# JEEP_Aux_Control_PCB.net
KiCad netlist of a schematic drawn in EAGLE
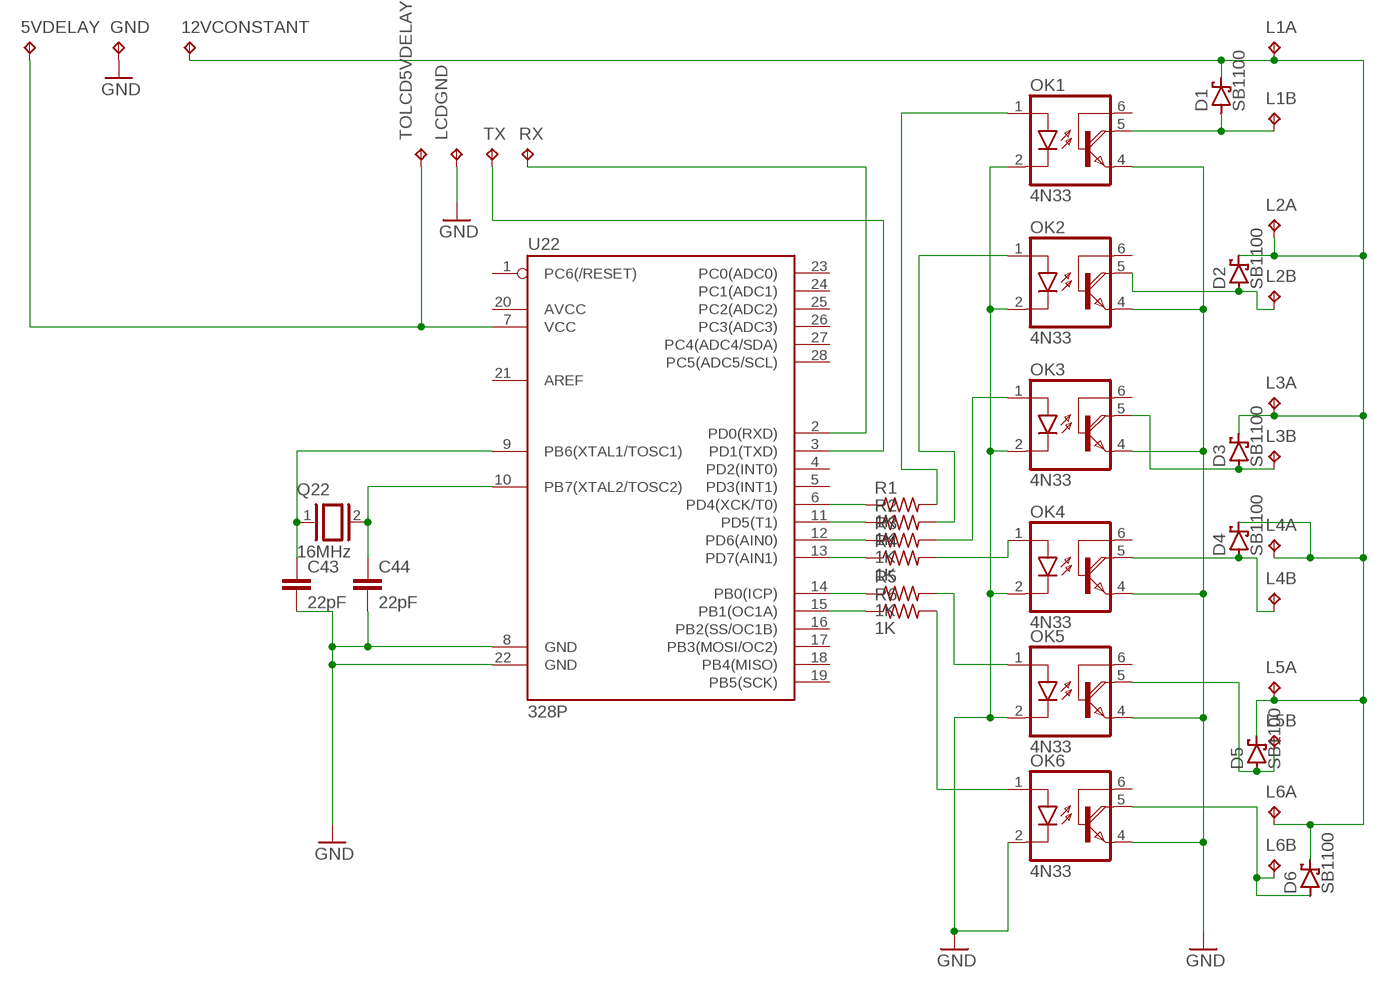
[diagram p0: schematic, sheet 1]

(export (version "E")
  (design (tool "Eeschema 10.0.6"))
  (components
    (comp (ref "5VDELAY")
      (value "TPPAD1-13Y")
      (footprint "eagle-import:P1-13Y")
      (libsource (lib "eagle-import") (part "TPPAD1-13Y"))
    )
    (comp (ref "12VCONSTANT")
      (value "TPPAD1-13Y")
      (footprint "eagle-import:P1-13Y")
      (libsource (lib "eagle-import") (part "TPPAD1-13Y"))
    )
    (comp (ref "C43")
      (value "22pF")
      (footprint "eagle-import:CAP-PTH-2.54")
      (libsource (lib "eagle-import") (part "22PF-PTH-2.54MM-200V-5%"))
    )
    (comp (ref "C44")
      (value "22pF")
      (footprint "eagle-import:CAP-PTH-2.54")
      (libsource (lib "eagle-import") (part "22PF-PTH-2.54MM-200V-5%"))
    )
    (comp (ref "D1")
      (value "SB1100")
      (footprint "eagle-import:CB417-15")
      (libsource (lib "eagle-import") (part "SCHOTTKY-DIODECB417-15"))
    )
    (comp (ref "D2")
      (value "SB1100")
      (footprint "eagle-import:CB417-15")
      (libsource (lib "eagle-import") (part "SCHOTTKY-DIODECB417-15"))
    )
    (comp (ref "D3")
      (value "SB1100")
      (footprint "eagle-import:CB417-15")
      (libsource (lib "eagle-import") (part "SCHOTTKY-DIODECB417-15"))
    )
    (comp (ref "D4")
      (value "SB1100")
      (footprint "eagle-import:CB417-15")
      (libsource (lib "eagle-import") (part "SCHOTTKY-DIODECB417-15"))
    )
    (comp (ref "D5")
      (value "SB1100")
      (footprint "eagle-import:CB417-15")
      (libsource (lib "eagle-import") (part "SCHOTTKY-DIODECB417-15"))
    )
    (comp (ref "D6")
      (value "SB1100")
      (footprint "eagle-import:CB417-15")
      (libsource (lib "eagle-import") (part "SCHOTTKY-DIODECB417-15"))
    )
    (comp (ref "GND")
      (value "TPPAD1-13Y")
      (footprint "eagle-import:P1-13Y")
      (libsource (lib "eagle-import") (part "TPPAD1-13Y"))
    )
    (comp (ref "L1A")
      (value "TPPAD1-13Y")
      (footprint "eagle-import:P1-13Y")
      (libsource (lib "eagle-import") (part "TPPAD1-13Y"))
    )
    (comp (ref "L1B")
      (value "TPPAD1-13Y")
      (footprint "eagle-import:P1-13Y")
      (libsource (lib "eagle-import") (part "TPPAD1-13Y"))
    )
    (comp (ref "L2A")
      (value "TPPAD1-13Y")
      (footprint "eagle-import:P1-13Y")
      (libsource (lib "eagle-import") (part "TPPAD1-13Y"))
    )
    (comp (ref "L2B")
      (value "TPPAD1-13Y")
      (footprint "eagle-import:P1-13Y")
      (libsource (lib "eagle-import") (part "TPPAD1-13Y"))
    )
    (comp (ref "L3A")
      (value "TPPAD1-13Y")
      (footprint "eagle-import:P1-13Y")
      (libsource (lib "eagle-import") (part "TPPAD1-13Y"))
    )
    (comp (ref "L3B")
      (value "TPPAD1-13Y")
      (footprint "eagle-import:P1-13Y")
      (libsource (lib "eagle-import") (part "TPPAD1-13Y"))
    )
    (comp (ref "L4A")
      (value "TPPAD1-13Y")
      (footprint "eagle-import:P1-13Y")
      (libsource (lib "eagle-import") (part "TPPAD1-13Y"))
    )
    (comp (ref "L4B")
      (value "TPPAD1-13Y")
      (footprint "eagle-import:P1-13Y")
      (libsource (lib "eagle-import") (part "TPPAD1-13Y"))
    )
    (comp (ref "L5A")
      (value "TPPAD1-13Y")
      (footprint "eagle-import:P1-13Y")
      (libsource (lib "eagle-import") (part "TPPAD1-13Y"))
    )
    (comp (ref "L5B")
      (value "TPPAD1-13Y")
      (footprint "eagle-import:P1-13Y")
      (libsource (lib "eagle-import") (part "TPPAD1-13Y"))
    )
    (comp (ref "L6A")
      (value "TPPAD1-13Y")
      (footprint "eagle-import:P1-13Y")
      (libsource (lib "eagle-import") (part "TPPAD1-13Y"))
    )
    (comp (ref "L6B")
      (value "TPPAD1-13Y")
      (footprint "eagle-import:P1-13Y")
      (libsource (lib "eagle-import") (part "TPPAD1-13Y"))
    )
    (comp (ref "LCDGND")
      (value "TPPAD1-13Y")
      (footprint "eagle-import:P1-13Y")
      (libsource (lib "eagle-import") (part "TPPAD1-13Y"))
    )
    (comp (ref "OK1")
      (value "4N33")
      (footprint "eagle-import:DIL06")
      (fields (field (name "MF") "VISHAY/TELEFUNKEN"))
      (libsource (lib "eagle-import") (part "4N33"))
    )
    (comp (ref "OK2")
      (value "4N33")
      (footprint "eagle-import:DIL06")
      (fields (field (name "MF") "VISHAY/TELEFUNKEN"))
      (libsource (lib "eagle-import") (part "4N33"))
    )
    (comp (ref "OK3")
      (value "4N33")
      (footprint "eagle-import:DIL06")
      (fields (field (name "MF") "VISHAY/TELEFUNKEN"))
      (libsource (lib "eagle-import") (part "4N33"))
    )
    (comp (ref "OK4")
      (value "4N33")
      (footprint "eagle-import:DIL06")
      (fields (field (name "MF") "VISHAY/TELEFUNKEN"))
      (libsource (lib "eagle-import") (part "4N33"))
    )
    (comp (ref "OK5")
      (value "4N33")
      (footprint "eagle-import:DIL06")
      (fields (field (name "MF") "VISHAY/TELEFUNKEN"))
      (libsource (lib "eagle-import") (part "4N33"))
    )
    (comp (ref "OK6")
      (value "4N33")
      (footprint "eagle-import:DIL06")
      (fields (field (name "MF") "VISHAY/TELEFUNKEN"))
      (libsource (lib "eagle-import") (part "4N33"))
    )
    (comp (ref "Q22")
      (value "16MHz")
      (footprint "eagle-import:Q")
      (libsource (lib "eagle-import") (part "XTAL"))
    )
    (comp (ref "R1")
      (value "1K")
      (footprint "eagle-import:R0603")
      (libsource (lib "eagle-import") (part "R-US_R0603"))
    )
    (comp (ref "R2")
      (value "1K")
      (footprint "eagle-import:R0603")
      (libsource (lib "eagle-import") (part "R-US_R0603"))
    )
    (comp (ref "R3")
      (value "1K")
      (footprint "eagle-import:R0603")
      (libsource (lib "eagle-import") (part "R-US_R0603"))
    )
    (comp (ref "R4")
      (value "1K")
      (footprint "eagle-import:R0603")
      (libsource (lib "eagle-import") (part "R-US_R0603"))
    )
    (comp (ref "R5")
      (value "1K")
      (footprint "eagle-import:R0603")
      (libsource (lib "eagle-import") (part "R-US_R0603"))
    )
    (comp (ref "R6")
      (value "1K")
      (footprint "eagle-import:R0603")
      (libsource (lib "eagle-import") (part "R-US_R0603"))
    )
    (comp (ref "RX")
      (value "TPPAD1-13Y")
      (footprint "eagle-import:P1-13Y")
      (libsource (lib "eagle-import") (part "TPPAD1-13Y"))
    )
    (comp (ref "TOLCD5VDELAY")
      (value "TPPAD1-13Y")
      (footprint "eagle-import:P1-13Y")
      (libsource (lib "eagle-import") (part "TPPAD1-13Y"))
    )
    (comp (ref "TX")
      (value "TPPAD1-13Y")
      (footprint "eagle-import:P1-13Y")
      (libsource (lib "eagle-import") (part "TPPAD1-13Y"))
    )
    (comp (ref "U22")
      (value "328P")
      (footprint "eagle-import:DIP28")
      (libsource (lib "eagle-import") (part "ATMEGA328P_PDIP"))
    )
  )
  (nets
    (net (code "1") (name "GND") (class "Default")
      (node (ref "C43") (pin "2") (pinfunction "2_2") (pintype "passive"))
      (node (ref "C44") (pin "2") (pinfunction "2_2") (pintype "passive"))
      (node (ref "GND") (pin "TP") (pinfunction "TP_TP") (pintype "input"))
      (node (ref "LCDGND") (pin "TP") (pinfunction "TP_TP") (pintype "input"))
      (node (ref "OK1") (pin "2") (pinfunction "C_2") (pintype "passive"))
      (node (ref "OK1") (pin "4") (pinfunction "E_4") (pintype "passive"))
      (node (ref "OK2") (pin "2") (pinfunction "C_2") (pintype "passive"))
      (node (ref "OK2") (pin "4") (pinfunction "E_4") (pintype "passive"))
      (node (ref "OK3") (pin "2") (pinfunction "C_2") (pintype "passive"))
      (node (ref "OK3") (pin "4") (pinfunction "E_4") (pintype "passive"))
      (node (ref "OK4") (pin "2") (pinfunction "C_2") (pintype "passive"))
      (node (ref "OK4") (pin "4") (pinfunction "E_4") (pintype "passive"))
      (node (ref "OK5") (pin "2") (pinfunction "C_2") (pintype "passive"))
      (node (ref "OK5") (pin "4") (pinfunction "E_4") (pintype "passive"))
      (node (ref "OK6") (pin "2") (pinfunction "C_2") (pintype "passive"))
      (node (ref "OK6") (pin "4") (pinfunction "E_4") (pintype "passive"))
      (node (ref "U22") (pin "22") (pinfunction "GND_22") (pintype "bidirectional"))
      (node (ref "U22") (pin "8") (pinfunction "GND_8") (pintype "bidirectional"))
    )
    (net (code "2") (name "Net-(12VCONSTANT-PadTP)") (class "Default")
      (node (ref "12VCONSTANT") (pin "TP") (pinfunction "TP_TP") (pintype "input"))
      (node (ref "D1") (pin "C") (pinfunction "C_C") (pintype "passive"))
      (node (ref "D2") (pin "C") (pinfunction "C_C") (pintype "passive"))
      (node (ref "D3") (pin "C") (pinfunction "C_C") (pintype "passive"))
      (node (ref "D4") (pin "C") (pinfunction "C_C") (pintype "passive"))
      (node (ref "D5") (pin "C") (pinfunction "C_C") (pintype "passive"))
      (node (ref "D6") (pin "C") (pinfunction "C_C") (pintype "passive"))
      (node (ref "L1A") (pin "TP") (pinfunction "TP_TP") (pintype "input"))
      (node (ref "L2A") (pin "TP") (pinfunction "TP_TP") (pintype "input"))
      (node (ref "L3A") (pin "TP") (pinfunction "TP_TP") (pintype "input"))
      (node (ref "L4A") (pin "TP") (pinfunction "TP_TP") (pintype "input"))
      (node (ref "L5A") (pin "TP") (pinfunction "TP_TP") (pintype "input"))
      (node (ref "L6A") (pin "TP") (pinfunction "TP_TP") (pintype "input"))
    )
    (net (code "3") (name "Net-(OK1-A)") (class "Default")
      (node (ref "OK1") (pin "1") (pinfunction "A_1") (pintype "passive"))
      (node (ref "R1") (pin "2") (pinfunction "2_2") (pintype "passive"))
    )
    (net (code "4") (name "Net-(OK1-COL)") (class "Default")
      (node (ref "D1") (pin "A") (pinfunction "A_A") (pintype "passive"))
      (node (ref "L1B") (pin "TP") (pinfunction "TP_TP") (pintype "input"))
      (node (ref "OK1") (pin "5") (pinfunction "COL_5") (pintype "passive"))
    )
    (net (code "5") (name "Net-(OK2-A)") (class "Default")
      (node (ref "OK2") (pin "1") (pinfunction "A_1") (pintype "passive"))
      (node (ref "R2") (pin "2") (pinfunction "2_2") (pintype "passive"))
    )
    (net (code "6") (name "Net-(OK2-COL)") (class "Default")
      (node (ref "D2") (pin "A") (pinfunction "A_A") (pintype "passive"))
      (node (ref "L2B") (pin "TP") (pinfunction "TP_TP") (pintype "input"))
      (node (ref "OK2") (pin "5") (pinfunction "COL_5") (pintype "passive"))
    )
    (net (code "7") (name "Net-(OK3-A)") (class "Default")
      (node (ref "OK3") (pin "1") (pinfunction "A_1") (pintype "passive"))
      (node (ref "R3") (pin "2") (pinfunction "2_2") (pintype "passive"))
    )
    (net (code "8") (name "Net-(OK3-COL)") (class "Default")
      (node (ref "D3") (pin "A") (pinfunction "A_A") (pintype "passive"))
      (node (ref "L3B") (pin "TP") (pinfunction "TP_TP") (pintype "input"))
      (node (ref "OK3") (pin "5") (pinfunction "COL_5") (pintype "passive"))
    )
    (net (code "9") (name "Net-(OK4-A)") (class "Default")
      (node (ref "OK4") (pin "1") (pinfunction "A_1") (pintype "passive"))
      (node (ref "R4") (pin "2") (pinfunction "2_2") (pintype "passive"))
    )
    (net (code "10") (name "Net-(OK4-COL)") (class "Default")
      (node (ref "D4") (pin "A") (pinfunction "A_A") (pintype "passive"))
      (node (ref "L4B") (pin "TP") (pinfunction "TP_TP") (pintype "input"))
      (node (ref "OK4") (pin "5") (pinfunction "COL_5") (pintype "passive"))
    )
    (net (code "11") (name "Net-(OK5-A)") (class "Default")
      (node (ref "OK5") (pin "1") (pinfunction "A_1") (pintype "passive"))
      (node (ref "R5") (pin "2") (pinfunction "2_2") (pintype "passive"))
    )
    (net (code "12") (name "Net-(OK5-COL)") (class "Default")
      (node (ref "D5") (pin "A") (pinfunction "A_A") (pintype "passive"))
      (node (ref "L5B") (pin "TP") (pinfunction "TP_TP") (pintype "input"))
      (node (ref "OK5") (pin "5") (pinfunction "COL_5") (pintype "passive"))
    )
    (net (code "13") (name "Net-(OK6-A)") (class "Default")
      (node (ref "OK6") (pin "1") (pinfunction "A_1") (pintype "passive"))
      (node (ref "R6") (pin "2") (pinfunction "2_2") (pintype "passive"))
    )
    (net (code "14") (name "Net-(OK6-COL)") (class "Default")
      (node (ref "D6") (pin "A") (pinfunction "A_A") (pintype "passive"))
      (node (ref "L6B") (pin "TP") (pinfunction "TP_TP") (pintype "input"))
      (node (ref "OK6") (pin "5") (pinfunction "COL_5") (pintype "passive"))
    )
    (net (code "15") (name "Net-(U22-PB0(ICP))") (class "Default")
      (node (ref "R5") (pin "1") (pinfunction "1_1") (pintype "passive"))
      (node (ref "U22") (pin "14") (pinfunction "PB0(ICP)_14") (pintype "bidirectional"))
    )
    (net (code "16") (name "Net-(U22-PB1(OC1A))") (class "Default")
      (node (ref "R6") (pin "1") (pinfunction "1_1") (pintype "passive"))
      (node (ref "U22") (pin "15") (pinfunction "PB1(OC1A)_15") (pintype "bidirectional"))
    )
    (net (code "17") (name "Net-(U22-PB6(XTAL1{slash}TOSC1))") (class "Default")
      (node (ref "C43") (pin "1") (pinfunction "1_1") (pintype "passive"))
      (node (ref "Q22") (pin "1") (pinfunction "1_1") (pintype "passive"))
      (node (ref "U22") (pin "9") (pinfunction "PB6(XTAL1/TOSC1)_9") (pintype "bidirectional"))
    )
    (net (code "18") (name "Net-(U22-PB7(XTAL2{slash}TOSC2))") (class "Default")
      (node (ref "C44") (pin "1") (pinfunction "1_1") (pintype "passive"))
      (node (ref "Q22") (pin "2") (pinfunction "2_2") (pintype "passive"))
      (node (ref "U22") (pin "10") (pinfunction "PB7(XTAL2/TOSC2)_10") (pintype "bidirectional"))
    )
    (net (code "19") (name "Net-(U22-PD0(RXD))") (class "Default")
      (node (ref "RX") (pin "TP") (pinfunction "TP_TP") (pintype "input"))
      (node (ref "U22") (pin "2") (pinfunction "PD0(RXD)_2") (pintype "bidirectional"))
    )
    (net (code "20") (name "Net-(U22-PD1(TXD))") (class "Default")
      (node (ref "TX") (pin "TP") (pinfunction "TP_TP") (pintype "input"))
      (node (ref "U22") (pin "3") (pinfunction "PD1(TXD)_3") (pintype "bidirectional"))
    )
    (net (code "21") (name "Net-(U22-PD4(XCK{slash}T0))") (class "Default")
      (node (ref "R1") (pin "1") (pinfunction "1_1") (pintype "passive"))
      (node (ref "U22") (pin "6") (pinfunction "PD4(XCK/T0)_6") (pintype "bidirectional"))
    )
    (net (code "22") (name "Net-(U22-PD5(T1))") (class "Default")
      (node (ref "R2") (pin "1") (pinfunction "1_1") (pintype "passive"))
      (node (ref "U22") (pin "11") (pinfunction "PD5(T1)_11") (pintype "bidirectional"))
    )
    (net (code "23") (name "Net-(U22-PD6(AIN0))") (class "Default")
      (node (ref "R3") (pin "1") (pinfunction "1_1") (pintype "passive"))
      (node (ref "U22") (pin "12") (pinfunction "PD6(AIN0)_12") (pintype "bidirectional"))
    )
    (net (code "24") (name "Net-(U22-PD7(AIN1))") (class "Default")
      (node (ref "R4") (pin "1") (pinfunction "1_1") (pintype "passive"))
      (node (ref "U22") (pin "13") (pinfunction "PD7(AIN1)_13") (pintype "bidirectional"))
    )
    (net (code "25") (name "Net-(U22-VCC)") (class "Default")
      (node (ref "5VDELAY") (pin "TP") (pinfunction "TP_TP") (pintype "input"))
      (node (ref "TOLCD5VDELAY") (pin "TP") (pinfunction "TP_TP") (pintype "input"))
      (node (ref "U22") (pin "7") (pinfunction "VCC_7") (pintype "bidirectional"))
    )
    (net (code "26") (name "unconnected-(OK1-B-Pad6)") (class "Default")
      (node (ref "OK1") (pin "6") (pinfunction "B_6") (pintype "passive"))
    )
    (net (code "27") (name "unconnected-(OK2-B-Pad6)") (class "Default")
      (node (ref "OK2") (pin "6") (pinfunction "B_6") (pintype "passive"))
    )
    (net (code "28") (name "unconnected-(OK3-B-Pad6)") (class "Default")
      (node (ref "OK3") (pin "6") (pinfunction "B_6") (pintype "passive"))
    )
    (net (code "29") (name "unconnected-(OK4-B-Pad6)") (class "Default")
      (node (ref "OK4") (pin "6") (pinfunction "B_6") (pintype "passive"))
    )
    (net (code "30") (name "unconnected-(OK5-B-Pad6)") (class "Default")
      (node (ref "OK5") (pin "6") (pinfunction "B_6") (pintype "passive"))
    )
    (net (code "31") (name "unconnected-(OK6-B-Pad6)") (class "Default")
      (node (ref "OK6") (pin "6") (pinfunction "B_6") (pintype "passive"))
    )
    (net (code "32") (name "unconnected-(U22-AREF-Pad21)") (class "Default")
      (node (ref "U22") (pin "21") (pinfunction "AREF_21") (pintype "bidirectional"))
    )
    (net (code "33") (name "unconnected-(U22-AVCC-Pad20)") (class "Default")
      (node (ref "U22") (pin "20") (pinfunction "AVCC_20") (pintype "bidirectional"))
    )
    (net (code "34") (name "unconnected-(U22-PB2(SS{slash}OC1B)-Pad16)") (class "Default")
      (node (ref "U22") (pin "16") (pinfunction "PB2(SS/OC1B)_16") (pintype "bidirectional"))
    )
    (net (code "35") (name "unconnected-(U22-PB3(MOSI{slash}OC2)-Pad17)") (class "Default")
      (node (ref "U22") (pin "17") (pinfunction "PB3(MOSI/OC2)_17") (pintype "bidirectional"))
    )
    (net (code "36") (name "unconnected-(U22-PB4(MISO)-Pad18)") (class "Default")
      (node (ref "U22") (pin "18") (pinfunction "PB4(MISO)_18") (pintype "bidirectional"))
    )
    (net (code "37") (name "unconnected-(U22-PB5(SCK)-Pad19)") (class "Default")
      (node (ref "U22") (pin "19") (pinfunction "PB5(SCK)_19") (pintype "bidirectional"))
    )
    (net (code "38") (name "unconnected-(U22-PC0(ADC0)-Pad23)") (class "Default")
      (node (ref "U22") (pin "23") (pinfunction "PC0(ADC0)_23") (pintype "bidirectional"))
    )
    (net (code "39") (name "unconnected-(U22-PC1(ADC1)-Pad24)") (class "Default")
      (node (ref "U22") (pin "24") (pinfunction "PC1(ADC1)_24") (pintype "bidirectional"))
    )
    (net (code "40") (name "unconnected-(U22-PC2(ADC2)-Pad25)") (class "Default")
      (node (ref "U22") (pin "25") (pinfunction "PC2(ADC2)_25") (pintype "bidirectional"))
    )
    (net (code "41") (name "unconnected-(U22-PC3(ADC3)-Pad26)") (class "Default")
      (node (ref "U22") (pin "26") (pinfunction "PC3(ADC3)_26") (pintype "bidirectional"))
    )
    (net (code "42") (name "unconnected-(U22-PC4(ADC4{slash}SDA)-Pad27)") (class "Default")
      (node (ref "U22") (pin "27") (pinfunction "PC4(ADC4/SDA)_27") (pintype "bidirectional"))
    )
    (net (code "43") (name "unconnected-(U22-PC5(ADC5{slash}SCL)-Pad28)") (class "Default")
      (node (ref "U22") (pin "28") (pinfunction "PC5(ADC5/SCL)_28") (pintype "bidirectional"))
    )
    (net (code "44") (name "unconnected-(U22-PC6({slash}RESET)-Pad1)") (class "Default")
      (node (ref "U22") (pin "1") (pinfunction "PC6(/RESET)_1") (pintype "bidirectional"))
    )
    (net (code "45") (name "unconnected-(U22-PD2(INT0)-Pad4)") (class "Default")
      (node (ref "U22") (pin "4") (pinfunction "PD2(INT0)_4") (pintype "bidirectional"))
    )
    (net (code "46") (name "unconnected-(U22-PD3(INT1)-Pad5)") (class "Default")
      (node (ref "U22") (pin "5") (pinfunction "PD3(INT1)_5") (pintype "bidirectional"))
    )
  )
)
